# CPLD.net
KiCad netlist of a schematic drawn in Altium Designer
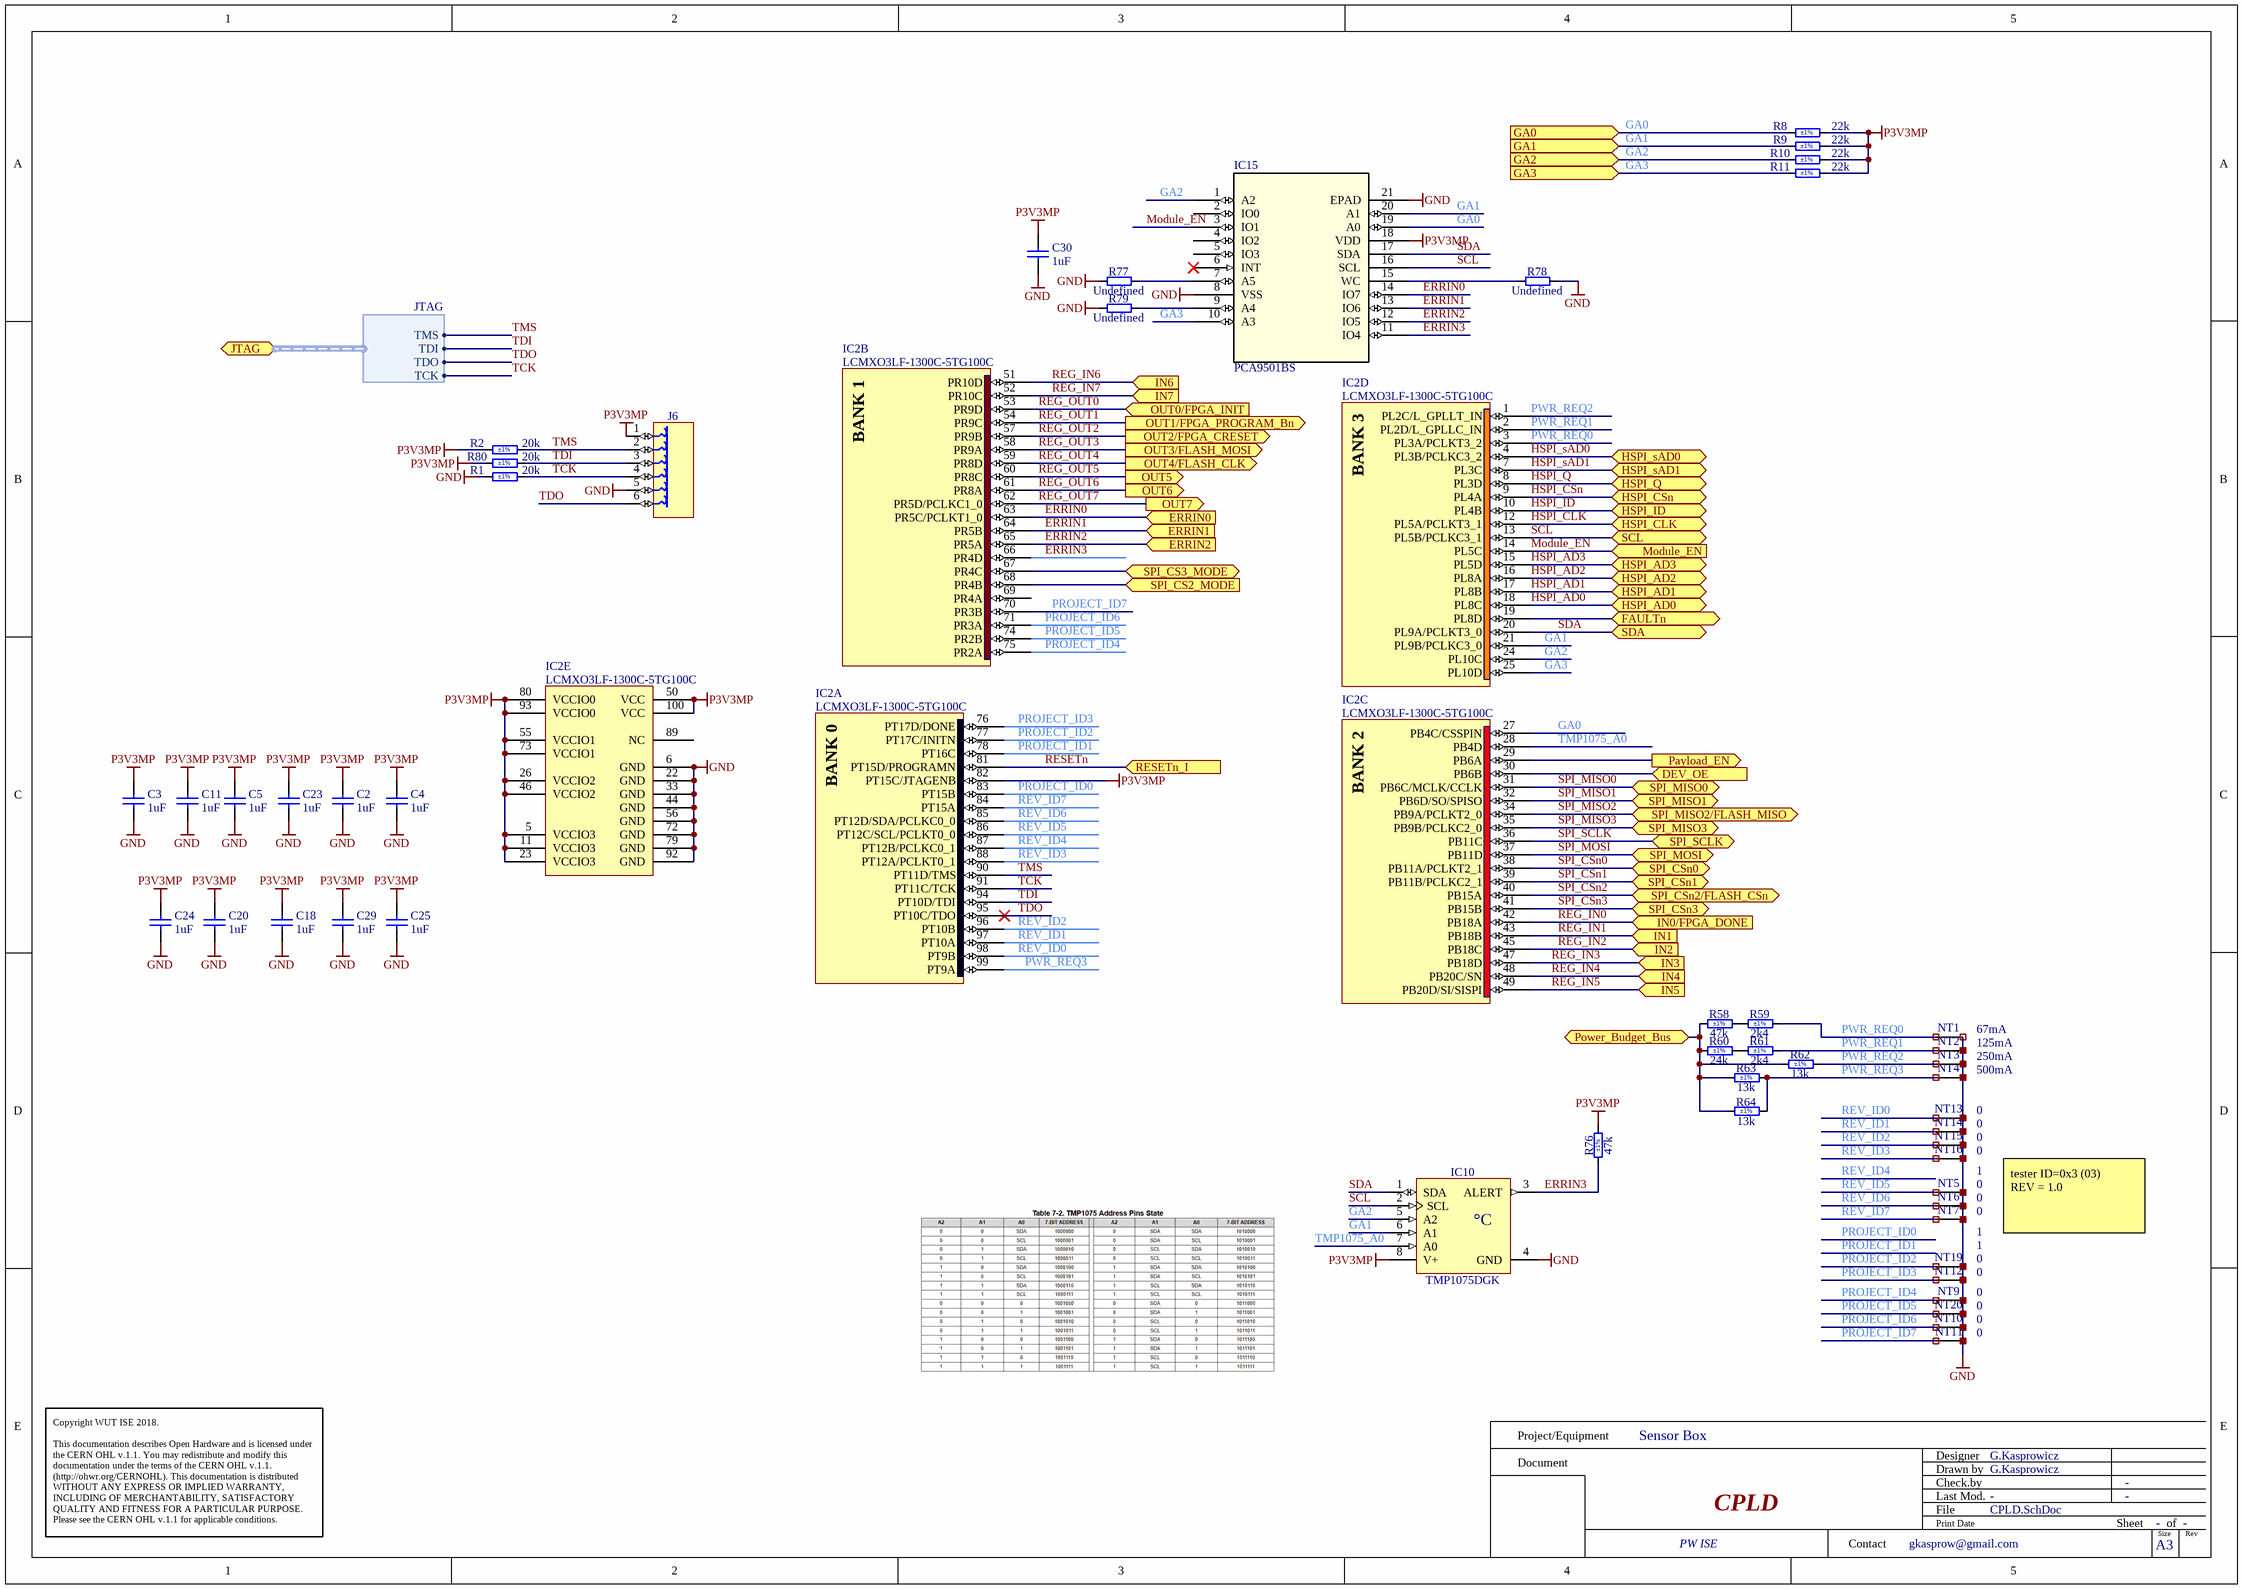
[diagram p0: CPLD.SchDoc]

(export (version "E")
  (design (tool "Eeschema 10.0.6"))
  (components
    (comp (ref "C2")
      (value "1uF")
      (footprint "CAPC1005X55N")
      (description "Non-polarised capacitor")
      (fields
        (field (name "PART NUMBER") "CC0402_1UF_16V_10%_X5R")
        (field (name "VOLTAGE") "16V")
        (field (name "AUTHOR") "CERN DEM JLC")
      )
      (libsource (lib "Capacitors") (part "Capacitor - non polarized"))
    )
    (comp (ref "C3")
      (value "1uF")
      (footprint "CAPC1005X55N")
      (description "Non-polarised capacitor")
      (fields
        (field (name "PART NUMBER") "CC0402_1UF_16V_10%_X5R")
        (field (name "VOLTAGE") "16V")
        (field (name "AUTHOR") "CERN DEM JLC")
      )
      (libsource (lib "Capacitors") (part "Capacitor - non polarized"))
    )
    (comp (ref "C4")
      (value "1uF")
      (footprint "CAPC1005X55N")
      (description "Non-polarised capacitor")
      (fields
        (field (name "PART NUMBER") "CC0402_1UF_16V_10%_X5R")
        (field (name "VOLTAGE") "16V")
        (field (name "AUTHOR") "CERN DEM JLC")
      )
      (libsource (lib "Capacitors") (part "Capacitor - non polarized"))
    )
    (comp (ref "C5")
      (value "1uF")
      (footprint "CAPC1005X55N")
      (description "Non-polarised capacitor")
      (fields
        (field (name "PART NUMBER") "CC0402_1UF_16V_10%_X5R")
        (field (name "VOLTAGE") "16V")
        (field (name "AUTHOR") "CERN DEM JLC")
      )
      (libsource (lib "Capacitors") (part "Capacitor - non polarized"))
    )
    (comp (ref "C11")
      (value "1uF")
      (footprint "CAPC1005X55N")
      (description "Non-polarised capacitor")
      (fields
        (field (name "PART NUMBER") "CC0402_1UF_16V_10%_X5R")
        (field (name "VOLTAGE") "16V")
        (field (name "AUTHOR") "CERN DEM JLC")
      )
      (libsource (lib "Capacitors") (part "Capacitor - non polarized"))
    )
    (comp (ref "C18")
      (value "1uF")
      (footprint "CAPC1005X55N")
      (description "Non-polarised capacitor")
      (fields
        (field (name "PART NUMBER") "CC0402_1UF_16V_10%_X5R")
        (field (name "VOLTAGE") "16V")
        (field (name "AUTHOR") "CERN DEM JLC")
      )
      (libsource (lib "Capacitors") (part "Capacitor - non polarized"))
    )
    (comp (ref "C20")
      (value "1uF")
      (footprint "CAPC1005X55N")
      (description "Non-polarised capacitor")
      (fields
        (field (name "PART NUMBER") "CC0402_1UF_16V_10%_X5R")
        (field (name "VOLTAGE") "16V")
        (field (name "AUTHOR") "CERN DEM JLC")
      )
      (libsource (lib "Capacitors") (part "Capacitor - non polarized"))
    )
    (comp (ref "C23")
      (value "1uF")
      (footprint "CAPC1005X55N")
      (description "Non-polarised capacitor")
      (fields
        (field (name "PART NUMBER") "CC0402_1UF_16V_10%_X5R")
        (field (name "VOLTAGE") "16V")
        (field (name "AUTHOR") "CERN DEM JLC")
      )
      (libsource (lib "Capacitors") (part "Capacitor - non polarized"))
    )
    (comp (ref "C24")
      (value "1uF")
      (footprint "CAPC1005X55N")
      (description "Non-polarised capacitor")
      (fields
        (field (name "PART NUMBER") "CC0402_1UF_16V_10%_X5R")
        (field (name "VOLTAGE") "16V")
        (field (name "AUTHOR") "CERN DEM JLC")
      )
      (libsource (lib "Capacitors") (part "Capacitor - non polarized"))
    )
    (comp (ref "C25")
      (value "1uF")
      (footprint "CAPC1005X55N")
      (description "Non-polarised capacitor")
      (fields
        (field (name "PART NUMBER") "CC0402_1UF_16V_10%_X5R")
        (field (name "VOLTAGE") "16V")
        (field (name "AUTHOR") "CERN DEM JLC")
      )
      (libsource (lib "Capacitors") (part "Capacitor - non polarized"))
    )
    (comp (ref "C29")
      (value "1uF")
      (footprint "CAPC1005X55N")
      (description "Non-polarised capacitor")
      (fields
        (field (name "PART NUMBER") "CC0402_1UF_16V_10%_X5R")
        (field (name "VOLTAGE") "16V")
        (field (name "AUTHOR") "CERN DEM JLC")
      )
      (libsource (lib "Capacitors") (part "Capacitor - non polarized"))
    )
    (comp (ref "C30")
      (value "1uF")
      (footprint "CAPC1005X55N")
      (description "Non-polarised capacitor")
      (fields
        (field (name "PART NUMBER") "CC0402_1UF_16V_10%_X5R")
        (field (name "VOLTAGE") "16V")
        (field (name "AUTHOR") "CERN DEM JLC")
      )
      (libsource (lib "Capacitors") (part "Capacitor - non polarized"))
    )
    (comp (ref "IC2")
      (value "LCMXO3LF-1300C-5TG100C")
      (footprint "QFP50P1600X1600X160-100N")
      (fields (field (name "MANUFACTURER") "LATTICE SEMICONDUCTOR") (field (name "AUTHOR") "CERN DEM MR"))
      (libsource (lib "ICs And Semiconductors") (part "LCMXO3LF-1300C-5TG100"))
    )
    (comp (ref "IC10")
      (value "TMP1075DGK")
      (footprint "SOP65P490X110-8N")
      (description "High Accuracy Temperature Sensor With I2C and SMBus Interface in Industry Standard LM75")
      (fields (field (name "MANUFACTURER") "TEXAS INSTRUMENTS") (field (name "AUTHOR") "CERN DEM MR"))
      (libsource (lib "ICs And Semiconductors") (part "TMP1075"))
    )
    (comp (ref "IC15")
      (value "PCA9501BS")
      (footprint "HVQFN20_SOT662-1_5X5_NXP")
      (description "8-bit I2C-bus and SMBus I/O port with interrupt, 2-kbit\r\nEEPROM and 6 address pins")
      (fields (field (name "MANUFACTURER") "NXP") (field (name "MANUFACTURER PART NUMBER") "PCA9501BS,118"))
      (libsource (lib "ICs_Analog_Interfaces") (part "IFC_PCA9501BS"))
    )
    (comp (ref "J6")
      (value "TC2030-MCP")
      (footprint "TC2030-MCP")
      (description "TC2030-MCP and TC2030-MCP-NL Pad Contact")
      (fields (field (name "AUTHOR") "CERN DEM HF"))
      (libsource (lib "Eletro-mechanical") (part "TC2030-MCP"))
    )
    (comp (ref "NT1")
      (value "Net Tie")
      (footprint "Net Tie 3")
      (fields (field (name "PART NUMBER") "Net Tie 3") (field (name "AUTHOR") "CERN DEM HF"))
      (libsource (lib "Eletro-mechanical") (part "Net Tie_a"))
    )
    (comp (ref "NT2")
      (value "Net Tie")
      (footprint "Net Tie 3")
      (fields (field (name "PART NUMBER") "Net Tie 3") (field (name "AUTHOR") "CERN DEM HF"))
      (libsource (lib "Eletro-mechanical") (part "Net Tie_a"))
    )
    (comp (ref "NT3")
      (value "Net Tie")
      (footprint "Net Tie 3")
      (fields (field (name "PART NUMBER") "Net Tie 3") (field (name "AUTHOR") "CERN DEM HF"))
      (libsource (lib "Eletro-mechanical") (part "Net Tie_a"))
    )
    (comp (ref "NT4")
      (value "Net Tie")
      (footprint "Net Tie 3")
      (fields (field (name "PART NUMBER") "Net Tie 3") (field (name "AUTHOR") "CERN DEM HF"))
      (libsource (lib "Eletro-mechanical") (part "Net Tie_a"))
    )
    (comp (ref "NT5")
      (value "Net Tie")
      (footprint "Net Tie 3")
      (fields (field (name "PART NUMBER") "Net Tie 3") (field (name "AUTHOR") "CERN DEM HF"))
      (libsource (lib "Eletro-mechanical") (part "Net Tie_a"))
    )
    (comp (ref "NT6")
      (value "Net Tie")
      (footprint "Net Tie 3")
      (fields (field (name "PART NUMBER") "Net Tie 3") (field (name "AUTHOR") "CERN DEM HF"))
      (libsource (lib "Eletro-mechanical") (part "Net Tie_a"))
    )
    (comp (ref "NT7")
      (value "Net Tie")
      (footprint "Net Tie 3")
      (fields (field (name "PART NUMBER") "Net Tie 3") (field (name "AUTHOR") "CERN DEM HF"))
      (libsource (lib "Eletro-mechanical") (part "Net Tie_a"))
    )
    (comp (ref "NT9")
      (value "Net Tie")
      (footprint "Net Tie 3")
      (fields (field (name "PART NUMBER") "Net Tie 3") (field (name "AUTHOR") "CERN DEM HF"))
      (libsource (lib "Eletro-mechanical") (part "Net Tie_a"))
    )
    (comp (ref "NT10")
      (value "Net Tie")
      (footprint "Net Tie 3")
      (fields (field (name "PART NUMBER") "Net Tie 3") (field (name "AUTHOR") "CERN DEM HF"))
      (libsource (lib "Eletro-mechanical") (part "Net Tie_a"))
    )
    (comp (ref "NT11")
      (value "Net Tie")
      (footprint "Net Tie 3")
      (fields (field (name "PART NUMBER") "Net Tie 3") (field (name "AUTHOR") "CERN DEM HF"))
      (libsource (lib "Eletro-mechanical") (part "Net Tie_a"))
    )
    (comp (ref "NT12")
      (value "Net Tie")
      (footprint "Net Tie 3")
      (fields (field (name "PART NUMBER") "Net Tie 3") (field (name "AUTHOR") "CERN DEM HF"))
      (libsource (lib "Eletro-mechanical") (part "Net Tie_a"))
    )
    (comp (ref "NT13")
      (value "Net Tie")
      (footprint "Net Tie 3")
      (fields (field (name "PART NUMBER") "Net Tie 3") (field (name "AUTHOR") "CERN DEM HF"))
      (libsource (lib "Eletro-mechanical") (part "Net Tie_a"))
    )
    (comp (ref "NT14")
      (value "Net Tie")
      (footprint "Net Tie 3")
      (fields (field (name "PART NUMBER") "Net Tie 3") (field (name "AUTHOR") "CERN DEM HF"))
      (libsource (lib "Eletro-mechanical") (part "Net Tie_a"))
    )
    (comp (ref "NT15")
      (value "Net Tie")
      (footprint "Net Tie 3")
      (fields (field (name "PART NUMBER") "Net Tie 3") (field (name "AUTHOR") "CERN DEM HF"))
      (libsource (lib "Eletro-mechanical") (part "Net Tie_a"))
    )
    (comp (ref "NT16")
      (value "Net Tie")
      (footprint "Net Tie 3")
      (fields (field (name "PART NUMBER") "Net Tie 3") (field (name "AUTHOR") "CERN DEM HF"))
      (libsource (lib "Eletro-mechanical") (part "Net Tie_a"))
    )
    (comp (ref "NT19")
      (value "Net Tie")
      (footprint "Net Tie 3")
      (fields (field (name "PART NUMBER") "Net Tie 3") (field (name "AUTHOR") "CERN DEM HF"))
      (libsource (lib "Eletro-mechanical") (part "Net Tie_a"))
    )
    (comp (ref "NT20")
      (value "Net Tie")
      (footprint "Net Tie 3")
      (fields (field (name "PART NUMBER") "Net Tie 3") (field (name "AUTHOR") "CERN DEM HF"))
      (libsource (lib "Eletro-mechanical") (part "Net Tie_a"))
    )
    (comp (ref "R1")
      (value "20k")
      (footprint "RESC1005X40N")
      (description "Resistor - 1%")
      (fields
        (field (name "TOLERANCE") "±1%")
        (field (name "PART NUMBER") "R0402_20K_1%_0.0625W_100PPM")
        (field (name "POWER") "0.0625W")
        (field (name "AUTHOR") "CERN DEM JLC")
      )
      (libsource (lib "Resistors") (part "Resistor - 1%"))
    )
    (comp (ref "R2")
      (value "20k")
      (footprint "RESC1005X40N")
      (description "Resistor - 1%")
      (fields
        (field (name "TOLERANCE") "±1%")
        (field (name "PART NUMBER") "R0402_20K_1%_0.0625W_100PPM")
        (field (name "POWER") "0.0625W")
        (field (name "AUTHOR") "CERN DEM JLC")
      )
      (libsource (lib "Resistors") (part "Resistor - 1%"))
    )
    (comp (ref "R8")
      (value "22k")
      (footprint "RESC1005X40N")
      (description "Resistor - 1%")
      (fields
        (field (name "TOLERANCE") "±1%")
        (field (name "PART NUMBER") "R0402_22K_1%_0.0625W_100PPM")
        (field (name "POWER") "0.0625W")
        (field (name "AUTHOR") "CERN DEM JLC")
      )
      (libsource (lib "Resistors") (part "Resistor - 1%"))
    )
    (comp (ref "R9")
      (value "22k")
      (footprint "RESC1005X40N")
      (description "Resistor - 1%")
      (fields
        (field (name "TOLERANCE") "±1%")
        (field (name "PART NUMBER") "R0402_22K_1%_0.0625W_100PPM")
        (field (name "POWER") "0.0625W")
        (field (name "AUTHOR") "CERN DEM JLC")
      )
      (libsource (lib "Resistors") (part "Resistor - 1%"))
    )
    (comp (ref "R10")
      (value "22k")
      (footprint "RESC1005X40N")
      (description "Resistor - 1%")
      (fields
        (field (name "TOLERANCE") "±1%")
        (field (name "PART NUMBER") "R0402_22K_1%_0.0625W_100PPM")
        (field (name "POWER") "0.0625W")
        (field (name "AUTHOR") "CERN DEM JLC")
      )
      (libsource (lib "Resistors") (part "Resistor - 1%"))
    )
    (comp (ref "R11")
      (value "22k")
      (footprint "RESC1005X40N")
      (description "Resistor - 1%")
      (fields
        (field (name "TOLERANCE") "±1%")
        (field (name "PART NUMBER") "R0402_22K_1%_0.0625W_100PPM")
        (field (name "POWER") "0.0625W")
        (field (name "AUTHOR") "CERN DEM JLC")
      )
      (libsource (lib "Resistors") (part "Resistor - 1%"))
    )
    (comp (ref "R58")
      (value "47k")
      (footprint "RESC1005X40N")
      (description "Resistor - 1%")
      (fields
        (field (name "TOLERANCE") "±1%")
        (field (name "PART NUMBER") "R0402_47K_1%_0.0625W_100PPM")
        (field (name "POWER") "0.0625W")
        (field (name "AUTHOR") "CERN DEM JLC")
      )
      (libsource (lib "Resistors") (part "Resistor - 1%"))
    )
    (comp (ref "R59")
      (value "2k4")
      (footprint "RESC1005X40N")
      (description "Resistor - 1%")
      (fields
        (field (name "TOLERANCE") "±1%")
        (field (name "PART NUMBER") "R0402_2K4_1%_0.0625W_100PPM")
        (field (name "POWER") "0.0625W")
        (field (name "AUTHOR") "CERN DEM JLC")
      )
      (libsource (lib "Resistors") (part "Resistor - 1%"))
    )
    (comp (ref "R60")
      (value "24k")
      (footprint "RESC1005X40N")
      (description "Resistor - 1%")
      (fields
        (field (name "TOLERANCE") "±1%")
        (field (name "PART NUMBER") "R0402_24K_1%_0.0625W_100PPM")
        (field (name "POWER") "0.0625W")
        (field (name "AUTHOR") "CERN DEM JLC")
      )
      (libsource (lib "Resistors") (part "Resistor - 1%"))
    )
    (comp (ref "R61")
      (value "2k4")
      (footprint "RESC1005X40N")
      (description "Resistor - 1%")
      (fields
        (field (name "TOLERANCE") "±1%")
        (field (name "PART NUMBER") "R0402_2K4_1%_0.0625W_100PPM")
        (field (name "POWER") "0.0625W")
        (field (name "AUTHOR") "CERN DEM JLC")
      )
      (libsource (lib "Resistors") (part "Resistor - 1%"))
    )
    (comp (ref "R62")
      (value "13k")
      (footprint "RESC1005X40N")
      (description "Resistor - 1%")
      (fields
        (field (name "TOLERANCE") "±1%")
        (field (name "PART NUMBER") "R0402_13K_1%_0.0625W_100PPM")
        (field (name "POWER") "0.0625W")
        (field (name "AUTHOR") "CERN DEM JLC")
      )
      (libsource (lib "Resistors") (part "Resistor - 1%"))
    )
    (comp (ref "R63")
      (value "13k")
      (footprint "RESC1005X40N")
      (description "Resistor - 1%")
      (fields
        (field (name "TOLERANCE") "±1%")
        (field (name "PART NUMBER") "R0402_13K_1%_0.0625W_100PPM")
        (field (name "POWER") "0.0625W")
        (field (name "AUTHOR") "CERN DEM JLC")
      )
      (libsource (lib "Resistors") (part "Resistor - 1%"))
    )
    (comp (ref "R64")
      (value "13k")
      (footprint "RESC1005X40N")
      (description "Resistor - 1%")
      (fields
        (field (name "TOLERANCE") "±1%")
        (field (name "PART NUMBER") "R0402_13K_1%_0.0625W_100PPM")
        (field (name "POWER") "0.0625W")
        (field (name "AUTHOR") "CERN DEM JLC")
      )
      (libsource (lib "Resistors") (part "Resistor - 1%"))
    )
    (comp (ref "R76")
      (value "47k")
      (footprint "RESC1005X40N")
      (description "Resistor - 1%")
      (fields
        (field (name "TOLERANCE") "±1%")
        (field (name "PART NUMBER") "R0402_47K_1%_0.0625W_100PPM")
        (field (name "POWER") "0.0625W")
        (field (name "AUTHOR") "CERN DEM JLC")
      )
      (libsource (lib "Resistors") (part "Resistor - 1%"))
    )
    (comp (ref "R77")
      (value "Undefined")
      (footprint "RESC1005X40N")
      (description "Resistor")
      (fields (field (name "PART NUMBER") "R0402_NO-VALUE") (field (name "AUTHOR") "CERN DEM JLC"))
      (libsource (lib "Resistors") (part "Resistor"))
    )
    (comp (ref "R78")
      (value "Undefined")
      (footprint "RESC1005X40N")
      (description "Resistor")
      (fields (field (name "PART NUMBER") "R0402_NO-VALUE") (field (name "AUTHOR") "CERN DEM JLC"))
      (libsource (lib "Resistors") (part "Resistor"))
    )
    (comp (ref "R79")
      (value "Undefined")
      (footprint "RESC1005X40N")
      (description "Resistor")
      (fields (field (name "PART NUMBER") "R0402_NO-VALUE") (field (name "AUTHOR") "CERN DEM JLC"))
      (libsource (lib "Resistors") (part "Resistor"))
    )
    (comp (ref "R80")
      (value "20k")
      (footprint "RESC1005X40N")
      (description "Resistor - 1%")
      (fields
        (field (name "TOLERANCE") "±1%")
        (field (name "PART NUMBER") "R0402_20K_1%_0.0625W_100PPM")
        (field (name "POWER") "0.0625W")
        (field (name "AUTHOR") "CERN DEM JLC")
      )
      (libsource (lib "Resistors") (part "Resistor - 1%"))
    )
  )
  (nets
    (net (code "2") (name "/DEV_OE") (class "Default")
      (node (ref "IC2") (pin "30") (pinfunction "PB6B_30") (pintype "bidirectional"))
    )
    (net (code "3") (name "/ERRIN0") (class "Default")
      (node (ref "IC15") (pin "14") (pinfunction "IO7_14") (pintype "bidirectional"))
      (node (ref "IC2") (pin "63") (pinfunction "PR5C/PCLKT1_0_63") (pintype "bidirectional"))
    )
    (net (code "4") (name "/ERRIN1") (class "Default")
      (node (ref "IC15") (pin "13") (pinfunction "IO6_13") (pintype "bidirectional"))
      (node (ref "IC2") (pin "64") (pinfunction "PR5B_64") (pintype "bidirectional"))
    )
    (net (code "5") (name "/ERRIN2") (class "Default")
      (node (ref "IC15") (pin "12") (pinfunction "IO5_12") (pintype "bidirectional"))
      (node (ref "IC2") (pin "65") (pinfunction "PR5A_65") (pintype "bidirectional"))
    )
    (net (code "6") (name "/ERRIN3") (class "Default")
      (node (ref "IC10") (pin "3") (pinfunction "ALERT_3") (pintype "output"))
      (node (ref "IC15") (pin "11") (pinfunction "IO4_11") (pintype "bidirectional"))
      (node (ref "IC2") (pin "66") (pinfunction "PR4D_66") (pintype "bidirectional"))
      (node (ref "R76") (pin "1") (pinfunction "1_1") (pintype "passive"))
    )
    (net (code "7") (name "/FAULTn") (class "Default")
      (node (ref "IC2") (pin "19") (pinfunction "PL8D_19") (pintype "bidirectional"))
    )
    (net (code "8") (name "/GA0") (class "Default")
      (node (ref "IC15") (pin "19") (pinfunction "A0_19") (pintype "bidirectional"))
      (node (ref "IC2") (pin "27") (pinfunction "PB4C/CSSPIN_27") (pintype "bidirectional"))
      (node (ref "R8") (pin "2") (pinfunction "2_2") (pintype "passive"))
    )
    (net (code "9") (name "/GA1") (class "Default")
      (node (ref "IC10") (pin "6") (pinfunction "A1_6") (pintype "input"))
      (node (ref "IC15") (pin "20") (pinfunction "A1_20") (pintype "bidirectional"))
      (node (ref "IC2") (pin "21") (pinfunction "PL9B/PCLKC3_0_21") (pintype "bidirectional"))
      (node (ref "R9") (pin "2") (pinfunction "2_2") (pintype "passive"))
    )
    (net (code "10") (name "/GA2") (class "Default")
      (node (ref "IC10") (pin "5") (pinfunction "A2_5") (pintype "input"))
      (node (ref "IC15") (pin "1") (pinfunction "A2_1") (pintype "bidirectional"))
      (node (ref "IC2") (pin "24") (pinfunction "PL10C_24") (pintype "bidirectional"))
      (node (ref "R10") (pin "2") (pinfunction "2_2") (pintype "passive"))
    )
    (net (code "11") (name "/GA3") (class "Default")
      (node (ref "IC15") (pin "10") (pinfunction "A3_10") (pintype "bidirectional"))
      (node (ref "IC2") (pin "25") (pinfunction "PL10D_25") (pintype "bidirectional"))
      (node (ref "R11") (pin "2") (pinfunction "2_2") (pintype "passive"))
    )
    (net (code "12") (name "/HSPI_AD0") (class "Default")
      (node (ref "IC2") (pin "18") (pinfunction "PL8C_18") (pintype "bidirectional"))
    )
    (net (code "13") (name "/HSPI_AD1") (class "Default")
      (node (ref "IC2") (pin "17") (pinfunction "PL8B_17") (pintype "bidirectional"))
    )
    (net (code "14") (name "/HSPI_AD2") (class "Default")
      (node (ref "IC2") (pin "16") (pinfunction "PL8A_16") (pintype "bidirectional"))
    )
    (net (code "15") (name "/HSPI_AD3") (class "Default")
      (node (ref "IC2") (pin "15") (pinfunction "PL5D_15") (pintype "bidirectional"))
    )
    (net (code "16") (name "/HSPI_CLK") (class "Default")
      (node (ref "IC2") (pin "12") (pinfunction "PL5A/PCLKT3_1_12") (pintype "bidirectional"))
    )
    (net (code "17") (name "/HSPI_CSn") (class "Default")
      (node (ref "IC2") (pin "9") (pinfunction "PL4A_9") (pintype "bidirectional"))
    )
    (net (code "18") (name "/HSPI_ID") (class "Default")
      (node (ref "IC2") (pin "10") (pinfunction "PL4B_10") (pintype "bidirectional"))
    )
    (net (code "19") (name "/HSPI_Q") (class "Default")
      (node (ref "IC2") (pin "8") (pinfunction "PL3D_8") (pintype "bidirectional"))
    )
    (net (code "20") (name "/HSPI_sAD0") (class "Default")
      (node (ref "IC2") (pin "4") (pinfunction "PL3B/PCLKC3_2_4") (pintype "bidirectional"))
    )
    (net (code "21") (name "/HSPI_sAD1") (class "Default")
      (node (ref "IC2") (pin "7") (pinfunction "PL3C_7") (pintype "bidirectional"))
    )
    (net (code "22") (name "/Module_EN") (class "Default")
      (node (ref "IC15") (pin "3") (pinfunction "IO1_3") (pintype "bidirectional"))
      (node (ref "IC2") (pin "14") (pinfunction "PL5C_14") (pintype "bidirectional"))
    )
    (net (code "23") (name "/PROJECT_ID0") (class "Default")
      (node (ref "IC2") (pin "83") (pinfunction "PT15B_83") (pintype "bidirectional"))
    )
    (net (code "24") (name "/PROJECT_ID1") (class "Default")
      (node (ref "IC2") (pin "78") (pinfunction "PT16C_78") (pintype "bidirectional"))
    )
    (net (code "25") (name "/PROJECT_ID2") (class "Default")
      (node (ref "IC2") (pin "77") (pinfunction "PT17C/INITN_77") (pintype "bidirectional"))
      (node (ref "NT19") (pin "1") (pinfunction "1_1") (pintype "bidirectional"))
    )
    (net (code "26") (name "/PROJECT_ID3") (class "Default")
      (node (ref "IC2") (pin "76") (pinfunction "PT17D/DONE_76") (pintype "bidirectional"))
      (node (ref "NT12") (pin "1") (pinfunction "1_1") (pintype "bidirectional"))
    )
    (net (code "27") (name "/PROJECT_ID4") (class "Default")
      (node (ref "IC2") (pin "75") (pinfunction "PR2A_75") (pintype "bidirectional"))
      (node (ref "NT9") (pin "1") (pinfunction "1_1") (pintype "bidirectional"))
    )
    (net (code "28") (name "/PROJECT_ID5") (class "Default")
      (node (ref "IC2") (pin "74") (pinfunction "PR2B_74") (pintype "bidirectional"))
      (node (ref "NT20") (pin "1") (pinfunction "1_1") (pintype "bidirectional"))
    )
    (net (code "29") (name "/PROJECT_ID6") (class "Default")
      (node (ref "IC2") (pin "71") (pinfunction "PR3A_71") (pintype "bidirectional"))
      (node (ref "NT10") (pin "1") (pinfunction "1_1") (pintype "bidirectional"))
    )
    (net (code "30") (name "/PROJECT_ID7") (class "Default")
      (node (ref "IC2") (pin "70") (pinfunction "PR3B_70") (pintype "bidirectional"))
      (node (ref "NT11") (pin "1") (pinfunction "1_1") (pintype "bidirectional"))
    )
    (net (code "31") (name "/PWR_REQ0") (class "Default")
      (node (ref "IC2") (pin "3") (pinfunction "PL3A/PCLKT3_2_3") (pintype "bidirectional"))
      (node (ref "NT1") (pin "1") (pinfunction "1_1") (pintype "bidirectional"))
      (node (ref "R59") (pin "2") (pinfunction "2_2") (pintype "passive"))
    )
    (net (code "32") (name "/PWR_REQ1") (class "Default")
      (node (ref "IC2") (pin "2") (pinfunction "PL2D/L_GPLLC_IN_2") (pintype "bidirectional"))
      (node (ref "NT2") (pin "1") (pinfunction "1_1") (pintype "bidirectional"))
      (node (ref "R61") (pin "2") (pinfunction "2_2") (pintype "passive"))
    )
    (net (code "33") (name "/PWR_REQ2") (class "Default")
      (node (ref "IC2") (pin "1") (pinfunction "PL2C/L_GPLLT_IN_1") (pintype "bidirectional"))
      (node (ref "NT3") (pin "1") (pinfunction "1_1") (pintype "bidirectional"))
      (node (ref "R62") (pin "2") (pinfunction "2_2") (pintype "passive"))
    )
    (net (code "34") (name "/PWR_REQ3") (class "Default")
      (node (ref "IC2") (pin "99") (pinfunction "PT9A_99") (pintype "bidirectional"))
      (node (ref "NT4") (pin "1") (pinfunction "1_1") (pintype "bidirectional"))
      (node (ref "R63") (pin "2") (pinfunction "2_2") (pintype "passive"))
      (node (ref "R64") (pin "2") (pinfunction "2_2") (pintype "passive"))
    )
    (net (code "35") (name "/Payload_EN") (class "Default")
      (node (ref "IC2") (pin "29") (pinfunction "PB6A_29") (pintype "bidirectional"))
    )
    (net (code "36") (name "/Power_Budget_Bus") (class "Default")
      (node (ref "R58") (pin "1") (pinfunction "1_1") (pintype "passive"))
      (node (ref "R60") (pin "1") (pinfunction "1_1") (pintype "passive"))
      (node (ref "R62") (pin "1") (pinfunction "1_1") (pintype "passive"))
      (node (ref "R63") (pin "1") (pinfunction "1_1") (pintype "passive"))
      (node (ref "R64") (pin "1") (pinfunction "1_1") (pintype "passive"))
    )
    (net (code "37") (name "/REG_IN0") (class "Default")
      (node (ref "IC2") (pin "42") (pinfunction "PB18A_42") (pintype "bidirectional"))
    )
    (net (code "38") (name "/REG_IN1") (class "Default")
      (node (ref "IC2") (pin "43") (pinfunction "PB18B_43") (pintype "bidirectional"))
    )
    (net (code "39") (name "/REG_IN2") (class "Default")
      (node (ref "IC2") (pin "45") (pinfunction "PB18C_45") (pintype "bidirectional"))
    )
    (net (code "40") (name "/REG_IN3") (class "Default")
      (node (ref "IC2") (pin "47") (pinfunction "PB18D_47") (pintype "bidirectional"))
    )
    (net (code "41") (name "/REG_IN4") (class "Default")
      (node (ref "IC2") (pin "48") (pinfunction "PB20C/SN_48") (pintype "bidirectional"))
    )
    (net (code "42") (name "/REG_IN5") (class "Default")
      (node (ref "IC2") (pin "49") (pinfunction "PB20D/SI/SISPI_49") (pintype "bidirectional"))
    )
    (net (code "43") (name "/REG_IN6") (class "Default")
      (node (ref "IC2") (pin "51") (pinfunction "PR10D_51") (pintype "bidirectional"))
    )
    (net (code "44") (name "/REG_IN7") (class "Default")
      (node (ref "IC2") (pin "52") (pinfunction "PR10C_52") (pintype "bidirectional"))
    )
    (net (code "45") (name "/REG_OUT0") (class "Default")
      (node (ref "IC2") (pin "53") (pinfunction "PR9D_53") (pintype "bidirectional"))
    )
    (net (code "46") (name "/REG_OUT1") (class "Default")
      (node (ref "IC2") (pin "54") (pinfunction "PR9C_54") (pintype "bidirectional"))
    )
    (net (code "47") (name "/REG_OUT2") (class "Default")
      (node (ref "IC2") (pin "57") (pinfunction "PR9B_57") (pintype "bidirectional"))
    )
    (net (code "48") (name "/REG_OUT3") (class "Default")
      (node (ref "IC2") (pin "58") (pinfunction "PR9A_58") (pintype "bidirectional"))
    )
    (net (code "49") (name "/REG_OUT4") (class "Default")
      (node (ref "IC2") (pin "59") (pinfunction "PR8D_59") (pintype "bidirectional"))
    )
    (net (code "50") (name "/REG_OUT5") (class "Default")
      (node (ref "IC2") (pin "60") (pinfunction "PR8C_60") (pintype "bidirectional"))
    )
    (net (code "51") (name "/REG_OUT6") (class "Default")
      (node (ref "IC2") (pin "61") (pinfunction "PR8A_61") (pintype "bidirectional"))
    )
    (net (code "52") (name "/REG_OUT7") (class "Default")
      (node (ref "IC2") (pin "62") (pinfunction "PR5D/PCLKC1_0_62") (pintype "bidirectional"))
    )
    (net (code "53") (name "/RESETn") (class "Default")
      (node (ref "IC2") (pin "81") (pinfunction "PT15D/PROGRAMN_81") (pintype "bidirectional"))
    )
    (net (code "54") (name "/REV_ID0") (class "Default")
      (node (ref "IC2") (pin "98") (pinfunction "PT9B_98") (pintype "bidirectional"))
      (node (ref "NT13") (pin "1") (pinfunction "1_1") (pintype "bidirectional"))
    )
    (net (code "55") (name "/REV_ID1") (class "Default")
      (node (ref "IC2") (pin "97") (pinfunction "PT10A_97") (pintype "bidirectional"))
      (node (ref "NT14") (pin "1") (pinfunction "1_1") (pintype "bidirectional"))
    )
    (net (code "56") (name "/REV_ID2") (class "Default")
      (node (ref "IC2") (pin "96") (pinfunction "PT10B_96") (pintype "bidirectional"))
      (node (ref "NT15") (pin "1") (pinfunction "1_1") (pintype "bidirectional"))
    )
    (net (code "57") (name "/REV_ID3") (class "Default")
      (node (ref "IC2") (pin "88") (pinfunction "PT12A/PCLKT0_1_88") (pintype "bidirectional"))
      (node (ref "NT16") (pin "1") (pinfunction "1_1") (pintype "bidirectional"))
    )
    (net (code "58") (name "/REV_ID4") (class "Default")
      (node (ref "IC2") (pin "87") (pinfunction "PT12B/PCLKC0_1_87") (pintype "bidirectional"))
    )
    (net (code "59") (name "/REV_ID5") (class "Default")
      (node (ref "IC2") (pin "86") (pinfunction "PT12C/SCL/PCLKT0_0_86") (pintype "bidirectional"))
      (node (ref "NT5") (pin "1") (pinfunction "1_1") (pintype "bidirectional"))
    )
    (net (code "60") (name "/REV_ID6") (class "Default")
      (node (ref "IC2") (pin "85") (pinfunction "PT12D/SDA/PCLKC0_0_85") (pintype "bidirectional"))
      (node (ref "NT6") (pin "1") (pinfunction "1_1") (pintype "bidirectional"))
    )
    (net (code "61") (name "/REV_ID7") (class "Default")
      (node (ref "IC2") (pin "84") (pinfunction "PT15A_84") (pintype "bidirectional"))
      (node (ref "NT7") (pin "1") (pinfunction "1_1") (pintype "bidirectional"))
    )
    (net (code "62") (name "/SCL") (class "Default")
      (node (ref "IC10") (pin "2") (pinfunction "SCL_2") (pintype "input"))
      (node (ref "IC15") (pin "16") (pinfunction "SCL_16") (pintype "passive"))
      (node (ref "IC2") (pin "13") (pinfunction "PL5B/PCLKC3_1_13") (pintype "bidirectional"))
    )
    (net (code "63") (name "/SDA") (class "Default")
      (node (ref "IC10") (pin "1") (pinfunction "SDA_1") (pintype "bidirectional"))
      (node (ref "IC15") (pin "17") (pinfunction "SDA_17") (pintype "passive"))
      (node (ref "IC2") (pin "20") (pinfunction "PL9A/PCLKT3_0_20") (pintype "bidirectional"))
    )
    (net (code "64") (name "/SPI_CS2_MODE") (class "Default")
      (node (ref "IC2") (pin "68") (pinfunction "PR4B_68") (pintype "bidirectional"))
    )
    (net (code "65") (name "/SPI_CS3_MODE") (class "Default")
      (node (ref "IC2") (pin "67") (pinfunction "PR4C_67") (pintype "bidirectional"))
    )
    (net (code "66") (name "/SPI_CSn0") (class "Default")
      (node (ref "IC2") (pin "38") (pinfunction "PB11A/PCLKT2_1_38") (pintype "bidirectional"))
    )
    (net (code "67") (name "/SPI_CSn1") (class "Default")
      (node (ref "IC2") (pin "39") (pinfunction "PB11B/PCLKC2_1_39") (pintype "bidirectional"))
    )
    (net (code "68") (name "/SPI_CSn2") (class "Default")
      (node (ref "IC2") (pin "40") (pinfunction "PB15A_40") (pintype "bidirectional"))
    )
    (net (code "69") (name "/SPI_CSn3") (class "Default")
      (node (ref "IC2") (pin "41") (pinfunction "PB15B_41") (pintype "bidirectional"))
    )
    (net (code "70") (name "/SPI_MISO0") (class "Default")
      (node (ref "IC2") (pin "31") (pinfunction "PB6C/MCLK/CCLK_31") (pintype "bidirectional"))
    )
    (net (code "71") (name "/SPI_MISO1") (class "Default")
      (node (ref "IC2") (pin "32") (pinfunction "PB6D/SO/SPISO_32") (pintype "bidirectional"))
    )
    (net (code "72") (name "/SPI_MISO2") (class "Default")
      (node (ref "IC2") (pin "34") (pinfunction "PB9A/PCLKT2_0_34") (pintype "bidirectional"))
    )
    (net (code "73") (name "/SPI_MISO3") (class "Default")
      (node (ref "IC2") (pin "35") (pinfunction "PB9B/PCLKC2_0_35") (pintype "bidirectional"))
    )
    (net (code "74") (name "/SPI_MOSI") (class "Default")
      (node (ref "IC2") (pin "37") (pinfunction "PB11D_37") (pintype "bidirectional"))
    )
    (net (code "75") (name "/SPI_SCLK") (class "Default")
      (node (ref "IC2") (pin "36") (pinfunction "PB11C_36") (pintype "bidirectional"))
    )
    (net (code "76") (name "/TCK") (class "Default")
      (node (ref "IC2") (pin "91") (pinfunction "PT11C/TCK_91") (pintype "bidirectional"))
      (node (ref "J6") (pin "4") (pinfunction "4_4") (pintype "bidirectional"))
      (node (ref "R1") (pin "1") (pinfunction "1_1") (pintype "passive"))
    )
    (net (code "77") (name "/TDI") (class "Default")
      (node (ref "IC2") (pin "94") (pinfunction "PT10D/TDI_94") (pintype "bidirectional"))
      (node (ref "J6") (pin "3") (pinfunction "3_3") (pintype "bidirectional"))
      (node (ref "R80") (pin "1") (pinfunction "1_1") (pintype "passive"))
    )
    (net (code "78") (name "/TDO") (class "Default")
      (node (ref "IC2") (pin "95") (pinfunction "PT10C/TDO_95") (pintype "bidirectional"))
      (node (ref "J6") (pin "6") (pinfunction "6_6") (pintype "bidirectional"))
    )
    (net (code "79") (name "/TMP1075_A0") (class "Default")
      (node (ref "IC10") (pin "7") (pinfunction "A0_7") (pintype "input"))
      (node (ref "IC2") (pin "28") (pinfunction "PB4D_28") (pintype "bidirectional"))
    )
    (net (code "80") (name "/TMS") (class "Default")
      (node (ref "IC2") (pin "90") (pinfunction "PT11D/TMS_90") (pintype "bidirectional"))
      (node (ref "J6") (pin "2") (pinfunction "2_2") (pintype "bidirectional"))
      (node (ref "R2") (pin "1") (pinfunction "1_1") (pintype "passive"))
    )
    (net (code "82") (name "GND") (class "Default")
      (node (ref "C11") (pin "1") (pinfunction "1_1") (pintype "passive"))
      (node (ref "C18") (pin "1") (pinfunction "1_1") (pintype "passive"))
      (node (ref "C2") (pin "1") (pinfunction "1_1") (pintype "passive"))
      (node (ref "C20") (pin "1") (pinfunction "1_1") (pintype "passive"))
      (node (ref "C23") (pin "1") (pinfunction "1_1") (pintype "passive"))
      (node (ref "C24") (pin "1") (pinfunction "1_1") (pintype "passive"))
      (node (ref "C25") (pin "1") (pinfunction "1_1") (pintype "passive"))
      (node (ref "C29") (pin "1") (pinfunction "1_1") (pintype "passive"))
      (node (ref "C3") (pin "1") (pinfunction "1_1") (pintype "passive"))
      (node (ref "C30") (pin "1") (pinfunction "1_1") (pintype "passive"))
      (node (ref "C4") (pin "1") (pinfunction "1_1") (pintype "passive"))
      (node (ref "C5") (pin "1") (pinfunction "1_1") (pintype "passive"))
      (node (ref "IC10") (pin "4") (pinfunction "GND_4") (pintype "power_in"))
      (node (ref "IC15") (pin "21") (pinfunction "EPAD_21") (pintype "passive"))
      (node (ref "IC15") (pin "8") (pinfunction "VSS_8") (pintype "power_in"))
      (node (ref "IC2") (pin "22") (pinfunction "GND_22") (pintype "power_in"))
      (node (ref "IC2") (pin "33") (pinfunction "GND_33") (pintype "power_in"))
      (node (ref "IC2") (pin "44") (pinfunction "GND_44") (pintype "power_in"))
      (node (ref "IC2") (pin "56") (pinfunction "GND_56") (pintype "power_in"))
      (node (ref "IC2") (pin "6") (pinfunction "GND_6") (pintype "power_in"))
      (node (ref "IC2") (pin "72") (pinfunction "GND_72") (pintype "power_in"))
      (node (ref "IC2") (pin "79") (pinfunction "GND_79") (pintype "power_in"))
      (node (ref "IC2") (pin "92") (pinfunction "GND_92") (pintype "power_in"))
      (node (ref "J6") (pin "5") (pinfunction "5_5") (pintype "bidirectional"))
      (node (ref "NT1") (pin "2") (pinfunction "2_2") (pintype "bidirectional"))
      (node (ref "NT10") (pin "2") (pinfunction "2_2") (pintype "bidirectional"))
      (node (ref "NT11") (pin "2") (pinfunction "2_2") (pintype "bidirectional"))
      (node (ref "NT12") (pin "2") (pinfunction "2_2") (pintype "bidirectional"))
      (node (ref "NT13") (pin "2") (pinfunction "2_2") (pintype "bidirectional"))
      (node (ref "NT14") (pin "2") (pinfunction "2_2") (pintype "bidirectional"))
      (node (ref "NT15") (pin "2") (pinfunction "2_2") (pintype "bidirectional"))
      (node (ref "NT16") (pin "2") (pinfunction "2_2") (pintype "bidirectional"))
      (node (ref "NT19") (pin "2") (pinfunction "2_2") (pintype "bidirectional"))
      (node (ref "NT2") (pin "2") (pinfunction "2_2") (pintype "bidirectional"))
      (node (ref "NT20") (pin "2") (pinfunction "2_2") (pintype "bidirectional"))
      (node (ref "NT3") (pin "2") (pinfunction "2_2") (pintype "bidirectional"))
      (node (ref "NT4") (pin "2") (pinfunction "2_2") (pintype "bidirectional"))
      (node (ref "NT5") (pin "2") (pinfunction "2_2") (pintype "bidirectional"))
      (node (ref "NT6") (pin "2") (pinfunction "2_2") (pintype "bidirectional"))
      (node (ref "NT7") (pin "2") (pinfunction "2_2") (pintype "bidirectional"))
      (node (ref "NT9") (pin "2") (pinfunction "2_2") (pintype "bidirectional"))
      (node (ref "R1") (pin "2") (pinfunction "2_2") (pintype "passive"))
      (node (ref "R77") (pin "1") (pinfunction "1_1") (pintype "passive"))
      (node (ref "R78") (pin "2") (pinfunction "2_2") (pintype "passive"))
      (node (ref "R79") (pin "1") (pinfunction "1_1") (pintype "passive"))
    )
    (net (code "83") (name "Net-(IC15-A4)") (class "Default")
      (node (ref "IC15") (pin "9") (pinfunction "A4_9") (pintype "bidirectional"))
      (node (ref "R79") (pin "2") (pinfunction "2_2") (pintype "passive"))
    )
    (net (code "84") (name "Net-(IC15-A5)") (class "Default")
      (node (ref "IC15") (pin "7") (pinfunction "A5_7") (pintype "bidirectional"))
      (node (ref "R77") (pin "2") (pinfunction "2_2") (pintype "passive"))
    )
    (net (code "85") (name "Net-(IC15-WC)") (class "Default")
      (node (ref "IC15") (pin "15") (pinfunction "WC_15") (pintype "passive"))
      (node (ref "R78") (pin "1") (pinfunction "1_1") (pintype "passive"))
    )
    (net (code "86") (name "Net-(R58-Pad2)") (class "Default")
      (node (ref "R58") (pin "2") (pinfunction "2_2") (pintype "passive"))
      (node (ref "R59") (pin "1") (pinfunction "1_1") (pintype "passive"))
    )
    (net (code "87") (name "Net-(R60-Pad2)") (class "Default")
      (node (ref "R60") (pin "2") (pinfunction "2_2") (pintype "passive"))
      (node (ref "R61") (pin "1") (pinfunction "1_1") (pintype "passive"))
    )
    (net (code "88") (name "P3V3MP") (class "Default")
      (node (ref "C11") (pin "2") (pinfunction "2_2") (pintype "passive"))
      (node (ref "C18") (pin "2") (pinfunction "2_2") (pintype "passive"))
      (node (ref "C2") (pin "2") (pinfunction "2_2") (pintype "passive"))
      (node (ref "C20") (pin "2") (pinfunction "2_2") (pintype "passive"))
      (node (ref "C23") (pin "2") (pinfunction "2_2") (pintype "passive"))
      (node (ref "C24") (pin "2") (pinfunction "2_2") (pintype "passive"))
      (node (ref "C25") (pin "2") (pinfunction "2_2") (pintype "passive"))
      (node (ref "C29") (pin "2") (pinfunction "2_2") (pintype "passive"))
      (node (ref "C3") (pin "2") (pinfunction "2_2") (pintype "passive"))
      (node (ref "C30") (pin "2") (pinfunction "2_2") (pintype "passive"))
      (node (ref "C4") (pin "2") (pinfunction "2_2") (pintype "passive"))
      (node (ref "C5") (pin "2") (pinfunction "2_2") (pintype "passive"))
      (node (ref "IC10") (pin "8") (pinfunction "V+_8") (pintype "power_in"))
      (node (ref "IC15") (pin "18") (pinfunction "VDD_18") (pintype "power_in"))
      (node (ref "IC2") (pin "100") (pinfunction "VCC_100") (pintype "power_in"))
      (node (ref "IC2") (pin "11") (pinfunction "VCCIO3_11") (pintype "power_in"))
      (node (ref "IC2") (pin "23") (pinfunction "VCCIO3_23") (pintype "power_in"))
      (node (ref "IC2") (pin "26") (pinfunction "VCCIO2_26") (pintype "power_in"))
      (node (ref "IC2") (pin "46") (pinfunction "VCCIO2_46") (pintype "power_in"))
      (node (ref "IC2") (pin "5") (pinfunction "VCCIO3_5") (pintype "power_in"))
      (node (ref "IC2") (pin "50") (pinfunction "VCC_50") (pintype "power_in"))
      (node (ref "IC2") (pin "55") (pinfunction "VCCIO1_55") (pintype "power_in"))
      (node (ref "IC2") (pin "73") (pinfunction "VCCIO1_73") (pintype "power_in"))
      (node (ref "IC2") (pin "80") (pinfunction "VCCIO0_80") (pintype "power_in"))
      (node (ref "IC2") (pin "82") (pinfunction "PT15C/JTAGENB_82") (pintype "bidirectional"))
      (node (ref "IC2") (pin "93") (pinfunction "VCCIO0_93") (pintype "power_in"))
      (node (ref "J6") (pin "1") (pinfunction "1_1") (pintype "bidirectional"))
      (node (ref "R10") (pin "1") (pinfunction "1_1") (pintype "passive"))
      (node (ref "R11") (pin "1") (pinfunction "1_1") (pintype "passive"))
      (node (ref "R2") (pin "2") (pinfunction "2_2") (pintype "passive"))
      (node (ref "R76") (pin "2") (pinfunction "2_2") (pintype "passive"))
      (node (ref "R8") (pin "1") (pinfunction "1_1") (pintype "passive"))
      (node (ref "R80") (pin "2") (pinfunction "2_2") (pintype "passive"))
      (node (ref "R9") (pin "1") (pinfunction "1_1") (pintype "passive"))
    )
    (net (code "89") (name "unconnected-(IC2B-PR4A-Pad69)") (class "Default")
      (node (ref "IC2") (pin "69") (pinfunction "PR4A_69") (pintype "bidirectional"))
    )
    (net (code "90") (name "unconnected-(IC2E-NC-Pad89)") (class "Default")
      (node (ref "IC2") (pin "89") (pinfunction "NC_89") (pintype "passive"))
    )
    (net (code "91") (name "unconnected-(IC15-INT-Pad6)") (class "Default")
      (node (ref "IC15") (pin "6") (pinfunction "INT_6") (pintype "input+no_connect"))
    )
    (net (code "92") (name "unconnected-(IC15-IO0-Pad2)") (class "Default")
      (node (ref "IC15") (pin "2") (pinfunction "IO0_2") (pintype "bidirectional"))
    )
    (net (code "93") (name "unconnected-(IC15-IO2-Pad4)") (class "Default")
      (node (ref "IC15") (pin "4") (pinfunction "IO2_4") (pintype "bidirectional"))
    )
    (net (code "94") (name "unconnected-(IC15-IO3-Pad5)") (class "Default")
      (node (ref "IC15") (pin "5") (pinfunction "IO3_5") (pintype "bidirectional"))
    )
  )
)
